# WX0_011_323DL.net
KiCad netlist of a schematic drawn in Altium Designer
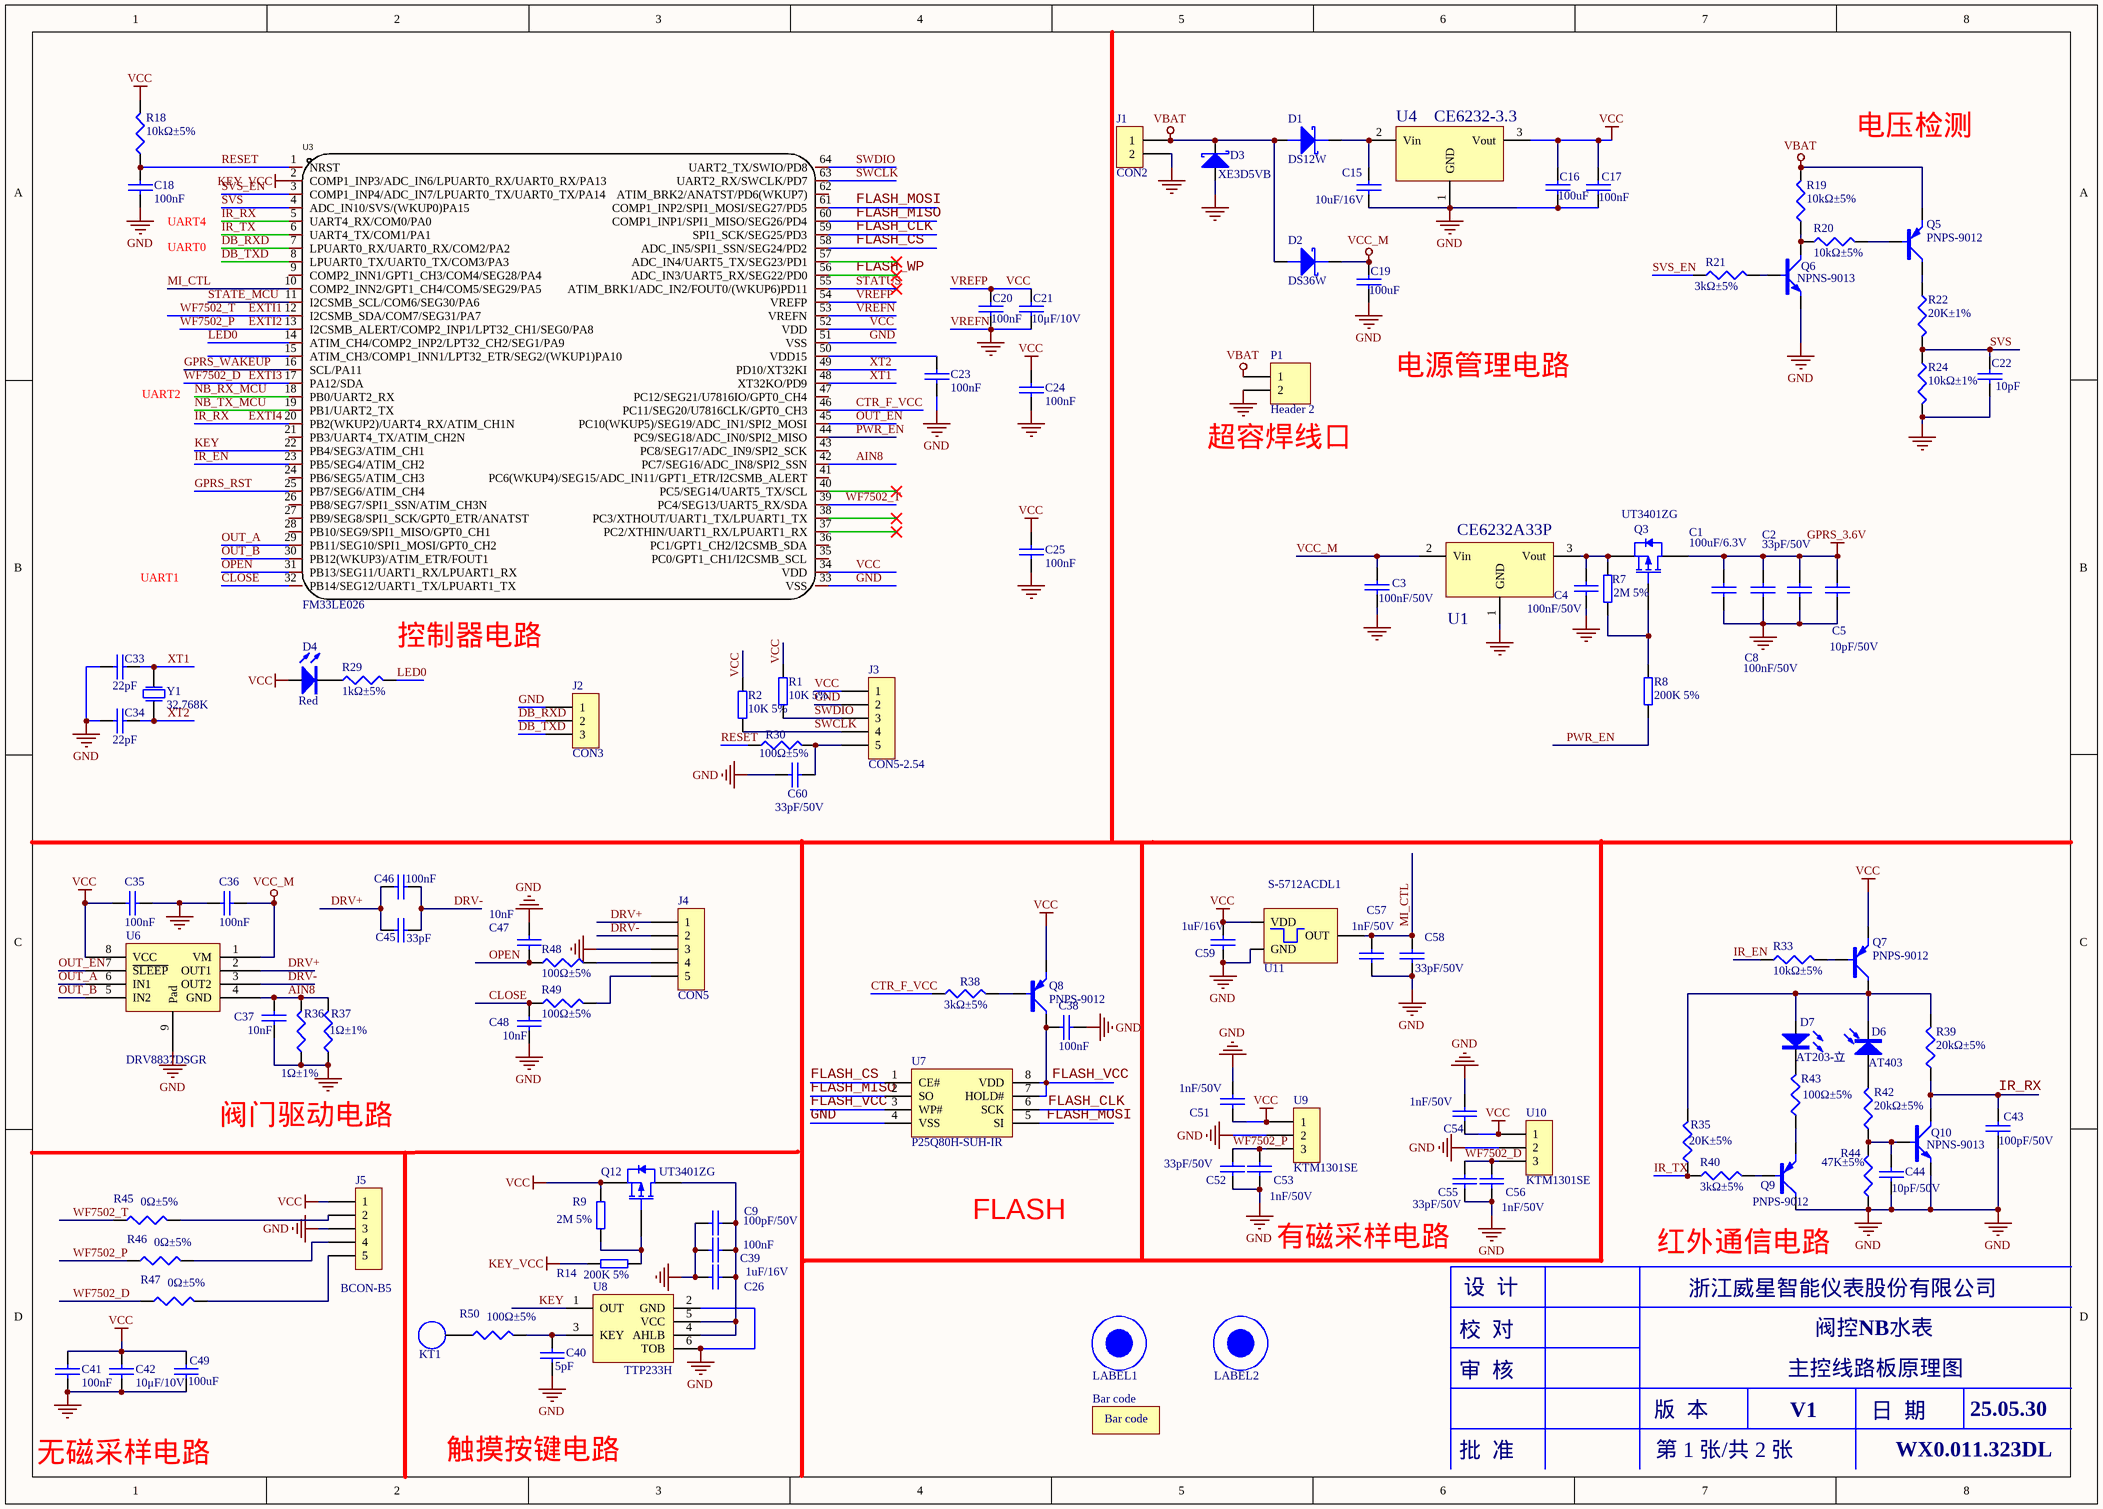
[diagram p0: WX0.011.323DL.SchDoc]

(export (version "E")
  (design (tool "Eeschema 10.0.6"))
  (components
    (comp (ref "Bar code")
      (value "Bar code")
      (footprint "Bar Code1")
      (libsource (lib "Connect_WX") (part "txm"))
    )
    (comp (ref "C1")
      (value "100uF/6.3V")
      (footprint "GRM1206")
      (description "100uF,6.3 V,±20%,1206,村田,GRM31CR60J107ME39L")
      (fields (field (name "PART NUMBER") "101020101-0020"))
      (libsource (lib "Database_Libs2") (part "CC06M5R5_107P"))
    )
    (comp (ref "C2")
      (value "33pF/50V")
      (footprint "CAP0603")
      (description "33pF,50 V,±10%,0603,国巨,CC0603KRNPO9BN33")
      (fields (field (name "PART NUMBER") "101020103-0027"))
      (libsource (lib "Database_Libs2") (part "CC03KPO9_33P"))
    )
    (comp (ref "C3")
      (value "100nF/50V")
      (footprint "CAP0603")
      (description "104pF,50 V,±10%,0603,国巨,CC0603KRX7R9BB104")
      (fields (field (name "PART NUMBER") "101020103-0021"))
      (libsource (lib "Database_Libs2") (part "CC03K7R9_100N"))
    )
    (comp (ref "C4")
      (value "100nF/50V")
      (footprint "CAP0603")
      (description "104pF,50 V,±10%,0603,国巨,CC0603KRX7R9BB104")
      (fields (field (name "PART NUMBER") "101020103-0021"))
      (libsource (lib "Database_Libs2") (part "CC03K7R9_100N"))
    )
    (comp (ref "C5")
      (value "10pF/50V")
      (footprint "CAP0603")
      (description "10pF,50 V,±5%,0603,X7R,国巨,CC0603JRNPO9BN100")
      (fields (field (name "PART NUMBER") "101020103-0014"))
      (libsource (lib "Database_Libs2") (part "CC03JPO9_10P"))
    )
    (comp (ref "C8")
      (value "100nF/50V")
      (footprint "CAP0603")
      (description "104pF,50 V,±10%,0603,国巨,CC0603KRX7R9BB104")
      (fields (field (name "PART NUMBER") "101020103-0021"))
      (libsource (lib "Database_Libs2") (part "CC03K7R9_100N"))
    )
    (comp (ref "C9")
      (value "100pF/50V")
      (footprint "CAP0603")
      (description "101pf,50 V,±5%,0603,国巨,CC0603JRNP09BN101")
      (fields (field (name "PART NUMBER") "101020103-0010"))
      (libsource (lib "Database_Libs2") (part "CC03JPO9_101P"))
    )
    (comp (ref "C15")
      (value "10uF/16V")
      (footprint "CAP0603")
      (description "105pF,16V,±10%,0603,国巨,CC0603KRX7R7BB105")
      (fields (field (name "PART NUMBER") "101020103-0003"))
      (libsource (lib "海外直通表U-GR3_GPRS") (part "CC03K7R7_1uF"))
    )
    (comp (ref "C16")
      (value "100uF")
      (footprint "GRM1206")
      (description "贴片电容,100uF±20%/6.3V,X5R,村田")
      (fields (field (name "PART NUMBER") "101020101-0020") (field (name "MANUFACTURER") "村田"))
      (libsource (lib "Devices") (part "CAP"))
    )
    (comp (ref "C17")
      (value "100nF")
      (footprint "CAP0603")
      (description "贴片电容,100nF±10%/50V,X7R,国巨")
      (fields (field (name "PART NUMBER") "101020103-0021") (field (name "MANUFACTURER") "国巨"))
      (libsource (lib "Devices") (part "CAP"))
    )
    (comp (ref "C18")
      (value "100nF")
      (footprint "CAP0603")
      (description "贴片电容,100nF±10%/50V,X7R,国巨")
      (fields (field (name "PART NUMBER") "101020103-0021") (field (name "MANUFACTURER") "国巨"))
      (libsource (lib "Devices") (part "CAP"))
    )
    (comp (ref "C19")
      (value "100uF")
      (footprint "GRM1206")
      (description "贴片电容,100uF±20%/6.3V,X5R,村田")
      (fields (field (name "PART NUMBER") "101020101-0020") (field (name "MANUFACTURER") "村田"))
      (libsource (lib "Devices") (part "CAP"))
    )
    (comp (ref "C20")
      (value "100nF")
      (footprint "CAP0603")
      (description "贴片电容,100nF±10%/50V,X7R,国巨")
      (fields (field (name "PART NUMBER") "101020103-0021") (field (name "MANUFACTURER") "国巨"))
      (libsource (lib "Devices") (part "CAP"))
    )
    (comp (ref "C21")
      (value "10μF/10V")
      (footprint "CAP0603")
      (description "贴片电容,10μF±10%/10V,X7R,村田")
      (fields (field (name "PART NUMBER") "101020103-0026") (field (name "MANUFACTURER") "村田"))
      (libsource (lib "Devices") (part "CAP"))
    )
    (comp (ref "C22")
      (value "10pF")
      (footprint "CAP0603")
      (description "贴片电容,12pF±5%/50V,NPO,国巨")
      (fields (field (name "PART NUMBER") "101020103-0005") (field (name "MANUFACTURER") "国巨"))
      (libsource (lib "Devices") (part "CAP"))
    )
    (comp (ref "C23")
      (value "100nF")
      (footprint "CAP0603")
      (description "贴片电容,100nF±10%/50V,X7R,国巨")
      (fields (field (name "PART NUMBER") "101020103-0021") (field (name "MANUFACTURER") "国巨"))
      (libsource (lib "Devices") (part "CAP"))
    )
    (comp (ref "C24")
      (value "100nF")
      (footprint "CAP0603")
      (description "贴片电容,100nF±10%/50V,X7R,国巨")
      (fields (field (name "PART NUMBER") "101020103-0021") (field (name "MANUFACTURER") "国巨"))
      (libsource (lib "Devices") (part "CAP"))
    )
    (comp (ref "C25")
      (value "100nF")
      (footprint "CAP0603")
      (description "贴片电容,100nF±10%/50V,X7R,国巨")
      (fields (field (name "PART NUMBER") "101020103-0021") (field (name "MANUFACTURER") "国巨"))
      (libsource (lib "Devices") (part "CAP"))
    )
    (comp (ref "C26")
      (value "1uF/16V")
      (footprint "CAP0603")
      (description "105pF,16 V,±10%,0603,国巨,CC0603KRX7R7BB105")
      (fields (field (name "PART NUMBER") "101020103-0003"))
      (libsource (lib "Database_Libs2") (part "CC03K7R7_1U"))
    )
    (comp (ref "C33")
      (value "22pF")
      (footprint "CAP0603")
      (description "贴片电容,22pF±5%/50V,NP0,国巨")
      (fields (field (name "PART NUMBER") "101020103-0009") (field (name "MANUFACTURER") "国巨"))
      (libsource (lib "Devices") (part "CAP"))
    )
    (comp (ref "C34")
      (value "22pF")
      (footprint "CAP0603")
      (description "贴片电容,22pF±5%/50V,NP0,国巨")
      (fields (field (name "PART NUMBER") "101020103-0009") (field (name "MANUFACTURER") "国巨"))
      (libsource (lib "Devices") (part "CAP"))
    )
    (comp (ref "C35")
      (value "100nF")
      (footprint "CAP0603")
      (description "贴片电容,100nF±10%/50V,X7R,国巨")
      (fields (field (name "PART NUMBER") "101020103-0021") (field (name "MANUFACTURER") "国巨"))
      (libsource (lib "Devices") (part "CAP"))
    )
    (comp (ref "C36")
      (value "100nF")
      (footprint "CAP0603")
      (description "贴片电容,100nF±10%/50V,X7R,国巨")
      (fields (field (name "PART NUMBER") "101020103-0021") (field (name "MANUFACTURER") "国巨"))
      (libsource (lib "Devices") (part "CAP"))
    )
    (comp (ref "C37")
      (value "10nF")
      (footprint "CAP0603")
      (description "贴片电容,10nF±10%/50V,X7R,国巨")
      (fields (field (name "PART NUMBER") "101020103-0007") (field (name "MANUFACTURER") "国巨"))
      (libsource (lib "Devices") (part "CAP"))
    )
    (comp (ref "C38")
      (value "100nF")
      (footprint "CAP0603")
      (description "贴片电容,100nF±10%/50V,X7R,国巨")
      (fields (field (name "PART NUMBER") "101020103-0021") (field (name "MANUFACTURER") "国巨"))
      (libsource (lib "Devices") (part "CAP"))
    )
    (comp (ref "C39")
      (value "100nF")
      (footprint "CAP0603")
      (description "贴片电容,100nF±10%/50V,X7R,国巨")
      (fields (field (name "PART NUMBER") "101020103-0021") (field (name "MANUFACTURER") "国巨"))
      (libsource (lib "Devices") (part "CAP"))
    )
    (comp (ref "C40")
      (value "5pF")
      (footprint "CAP0603")
      (description "贴片电容,4.7pF±0.25pF/50V,NPO,国巨")
      (fields (field (name "PART NUMBER") "101020103-0040") (field (name "MANUFACTURER") "国巨"))
      (libsource (lib "Devices") (part "CAP"))
    )
    (comp (ref "C41")
      (value "100nF")
      (footprint "CAP0603")
      (description "贴片电容,100nF±10%/50V,X7R,国巨")
      (fields (field (name "PART NUMBER") "101020103-0021") (field (name "MANUFACTURER") "国巨"))
      (libsource (lib "Devices") (part "CAP"))
    )
    (comp (ref "C42")
      (value "10μF/10V")
      (footprint "CAP0603")
      (description "贴片电容,1μF±10%/16V,X7R,国巨")
      (fields (field (name "PART NUMBER") "101020103-0003") (field (name "MANUFACTURER") "国巨"))
      (libsource (lib "Devices") (part "CAP"))
    )
    (comp (ref "C43")
      (value "100pF/50V")
      (footprint "CAP0603")
      (description "101pf,50 V,±5%,0603,国巨,CC0603JRNP09BN101")
      (fields (field (name "PART NUMBER") "101020103-0010"))
      (libsource (lib "Database_Libs2") (part "CC03JPO9_101P"))
    )
    (comp (ref "C44")
      (value "10pF/50V")
      (footprint "CAP0603")
      (description "10pF,50 V,±5%,0603,X7R,国巨,CC0603JRNPO9BN100")
      (fields (field (name "PART NUMBER") "101020103-0014"))
      (libsource (lib "Database_Libs2") (part "CC03JPO9_10P"))
    )
    (comp (ref "C45")
      (value "33pF")
      (footprint "CAP0603")
      (description "贴片电容,100nF±10%/50V,X7R,国巨")
      (fields (field (name "PART NUMBER") "101020103-0021") (field (name "MANUFACTURER") "国巨"))
      (libsource (lib "Devices") (part "CAP"))
    )
    (comp (ref "C46")
      (value "100nF")
      (footprint "CAP0603")
      (description "贴片电容,100nF±10%/50V,X7R,国巨")
      (fields (field (name "PART NUMBER") "101020103-0021") (field (name "MANUFACTURER") "国巨"))
      (libsource (lib "Devices") (part "CAP"))
    )
    (comp (ref "C47")
      (value "10nF")
      (footprint "CAP0603")
      (description "贴片电容,10nF±10%/50V,X7R,国巨")
      (fields (field (name "PART NUMBER") "101020103-0007") (field (name "MANUFACTURER") "国巨"))
      (libsource (lib "Devices") (part "CAP"))
    )
    (comp (ref "C48")
      (value "10nF")
      (footprint "CAP0603")
      (description "贴片电容,10nF±10%/50V,X7R,国巨")
      (fields (field (name "PART NUMBER") "101020103-0007") (field (name "MANUFACTURER") "国巨"))
      (libsource (lib "Devices") (part "CAP"))
    )
    (comp (ref "C49")
      (value "100uF")
      (footprint "GRM1206")
      (description "贴片电容,100uF±20%/6.3V,X5R,村田")
      (fields (field (name "PART NUMBER") "101020101-0020") (field (name "MANUFACTURER") "村田"))
      (libsource (lib "Devices") (part "CAP"))
    )
    (comp (ref "C51")
      (value "1nF/50V")
      (footprint "CAP0603")
      (description "102pF,50 V,±10%,0603,国巨,CC0603KRX7R9BB102")
      (fields (field (name "PART NUMBER") "101020103-0022"))
      (libsource (lib "Database_Libs2") (part "CC03K7R9_1N"))
    )
    (comp (ref "C52")
      (value "33pF/50V")
      (footprint "CAP0603")
      (description "33pF,50 V,±10%,0603,国巨,CC0603KRNPO9BN33")
      (fields (field (name "PART NUMBER") "101020103-0027"))
      (libsource (lib "Database_Libs2") (part "CC03KPO9_33P"))
    )
    (comp (ref "C53")
      (value "1nF/50V")
      (footprint "CAP0603")
      (description "102pF,50 V,±10%,0603,国巨,CC0603KRX7R9BB102")
      (fields (field (name "PART NUMBER") "101020103-0022"))
      (libsource (lib "Database_Libs2") (part "CC03K7R9_1N"))
    )
    (comp (ref "C54")
      (value "1nF/50V")
      (footprint "CAP0603")
      (description "102pF,50 V,±10%,0603,国巨,CC0603KRX7R9BB102")
      (fields (field (name "PART NUMBER") "101020103-0022"))
      (libsource (lib "Database_Libs2") (part "CC03K7R9_1N"))
    )
    (comp (ref "C55")
      (value "33pF/50V")
      (footprint "CAP0603")
      (description "33pF,50 V,±10%,0603,国巨,CC0603KRNPO9BN33")
      (fields (field (name "PART NUMBER") "101020103-0027"))
      (libsource (lib "Database_Libs2") (part "CC03KPO9_33P"))
    )
    (comp (ref "C56")
      (value "1nF/50V")
      (footprint "CAP0603")
      (description "102pF,50 V,±10%,0603,国巨,CC0603KRX7R9BB102")
      (fields (field (name "PART NUMBER") "101020103-0022"))
      (libsource (lib "Database_Libs2") (part "CC03K7R9_1N"))
    )
    (comp (ref "C57")
      (value "1nF/50V")
      (footprint "CAP0603")
      (description "102pF,50 V,±10%,0603,国巨,CC0603KRX7R9BB102")
      (fields (field (name "PART NUMBER") "101020103-0022"))
      (libsource (lib "Database_Libs2") (part "CC03K7R9_1N"))
    )
    (comp (ref "C58")
      (value "33pF/50V")
      (footprint "CAP0603")
      (description "33pF,50 V,±10%,0603,国巨,CC0603KRNPO9BN33")
      (fields (field (name "PART NUMBER") "101020103-0027"))
      (libsource (lib "Database_Libs2") (part "CC03KPO9_33P"))
    )
    (comp (ref "C59")
      (value "1uF/16V")
      (footprint "CAP0603")
      (description "105pF,16 V,±10%,0603,国巨,CC0603KRX7R7BB105")
      (fields (field (name "PART NUMBER") "101020103-0003"))
      (libsource (lib "Database_Libs2") (part "CC03K7R7_1U"))
    )
    (comp (ref "C60")
      (value "33pF/50V")
      (footprint "CAP0603")
      (description "33pF,50 V,±10%,0603,国巨,CC0603KRNPO9BN33")
      (fields (field (name "PART NUMBER") "101020103-0027"))
      (libsource (lib "Database_Libs2") (part "CC03KPO9_33P"))
    )
    (comp (ref "D1")
      (value "DS12W")
      (footprint "SOD-123FL")
      (description "DS36W,SOD123-FL,3 A,42 V,60 V,浙江领晨科技有限公司,DS36W")
      (fields (field (name "PART NUMBER") "101040101-0055"))
      (libsource (lib "Database_Libs2") (part "02_DS36W"))
    )
    (comp (ref "D2")
      (value "DS36W")
      (footprint "SOD-123FL")
      (description "DS36W,SOD123-FL,3 A,42 V,60 V,浙江领晨科技有限公司,DS36W")
      (fields (field (name "PART NUMBER") "101040101-0055"))
      (libsource (lib "Database_Libs2") (part "02_DS36W"))
    )
    (comp (ref "D3")
      (value "XE3D5VB")
      (footprint "SOD-323_L1.8-W1.3-LS2.5-RD")
      (description "具有3.5pF低结电容，适用于IO线、电源线、高速信号的ESD二极管阵列,SOD-323,5 V,5 V,350 W,5 A,1 uA,矽航,XE3D5VB")
      (fields (field (name "PART NUMBER") "101040104-0010") (field (name "MANUFACTURER") "矽航"))
      (libsource (lib "Devices") (part "DIODE1"))
    )
    (comp (ref "D4")
      (value "Red")
      (footprint "LED-0603")
      (description "发光二极管,红色,0603,光宝")
      (fields (field (name "PART NUMBER") "101040102-0006") (field (name "MANUFACTURER") "光宝"))
      (libsource (lib "Devices") (part "LED"))
    )
    (comp (ref "D6")
      (value "AT403")
      (footprint "LED2_300")
      (description "红外接收头，插件，红光，AT403_PD_01")
      (fields (field (name "PART NUMBER") "101040102-0011") (field (name "MANUFACTURER") "品观"))
      (libsource (lib "Devices") (part "LED_IN"))
    )
    (comp (ref "D7")
      (value "AT203-立")
      (footprint "LED2_300")
      (description "红外发射头，插件，红光，AT203")
      (fields (field (name "PART NUMBER") "101040102-0010") (field (name "MANUFACTURER") "品观"))
      (libsource (lib "") (part "LED_1"))
    )
    (comp (ref "J1")
      (value "CON2")
      (footprint "SIP-2")
      (description "焊接插座,间距2.54mm")
      (libsource (lib "Devices") (part "CON2"))
    )
    (comp (ref "J2")
      (value "CON3")
      (footprint "SIP-3")
      (description "焊接插座,间距2.54mm")
      (libsource (lib "Devices") (part "CON3"))
    )
    (comp (ref "J3")
      (value "CON5-2.54")
      (footprint "PIN254_1*5*1100S")
      (description "焊接插座,间距2.0mm")
      (libsource (lib "Devices") (part "CON5"))
    )
    (comp (ref "J4")
      (value "CON5")
      (footprint "PIN254_1*5*1100S")
      (description "焊接插座,间距2.54mm")
      (libsource (lib "Devices") (part "CON5"))
    )
    (comp (ref "J5")
      (value "BCON-B5")
      (footprint "J_DIP_2.0_1*05_H")
      (description "焊接插座,90度插板双面焊盘,公头,间距1.5mm")
      (libsource (lib "Devices") (part "CON5"))
    )
    (comp (ref "KT1")
      (value "Touch")
      (footprint "TOUCH-1")
      (description "按键,6mm弹簧按键,按键直径10mm")
      (fields (field (name "PART NUMBER") "1011001-0060"))
      (libsource (lib "Devices") (part "TOUCHKEY"))
    )
    (comp (ref "LABEL1")
      (value "~")
      (footprint "MARK")
      (description "标准Mark点,直径1mm,阻焊开窗3mm")
      (libsource (lib "Devices") (part "MARK"))
    )
    (comp (ref "LABEL2")
      (value "~")
      (footprint "MARK")
      (description "标准Mark点,直径1mm,阻焊开窗3mm")
      (libsource (lib "Devices") (part "MARK"))
    )
    (comp (ref "P1") (value "Header 2") (footprint "SIP-2") (libsource (lib "Connect_WX") (part "Header 2")))
    (comp (ref "Q3")
      (value "UT3401ZG")
      (footprint "SOT-23")
      (description "UT3401ZG,P-MOS,SOT-23,UTC,UT3401ZG")
      (fields (field (name "PART NUMBER") "101040201-0013"))
      (libsource (lib "Database_Libs2") (part "03_P-UT3401ZG"))
    )
    (comp (ref "Q5")
      (value "PNPS-9012")
      (footprint "SOT-23")
      (description "9012,PNP,SOT-23,JCET;长电,S9012")
      (fields (field (name "PART NUMBER") "101040201-0001"))
      (libsource (lib "Database_Libs2") (part "03_PNPS-9012"))
    )
    (comp (ref "Q6")
      (value "NPNS-9013")
      (footprint "SOT-23")
      (description "9013,NPN,SOT-23,长电,S9013")
      (fields (field (name "PART NUMBER") "101040201-0002"))
      (libsource (lib "Database_Libs2") (part "03_NPNS-9013"))
    )
    (comp (ref "Q7")
      (value "PNPS-9012")
      (footprint "SOT-23")
      (description "9012,PNP,SOT-23,JCET;长电,S9012")
      (fields (field (name "PART NUMBER") "101040201-0001"))
      (libsource (lib "Database_Libs2") (part "03_PNPS-9012"))
    )
    (comp (ref "Q8")
      (value "PNPS-9012")
      (footprint "SOT-23")
      (description "9012,PNP,SOT-23,JCET;长电,S9012")
      (fields (field (name "PART NUMBER") "101040201-0001"))
      (libsource (lib "Database_Libs2") (part "03_PNPS-9012"))
    )
    (comp (ref "Q9")
      (value "PNPS-9012")
      (footprint "SOT-23")
      (description "9012,PNP,SOT-23,JCET;长电,S9012")
      (fields (field (name "PART NUMBER") "101040201-0001"))
      (libsource (lib "Database_Libs2") (part "03_PNPS-9012"))
    )
    (comp (ref "Q10")
      (value "NPNS-9013")
      (footprint "SOT-23")
      (description "9013,NPN,SOT-23,长电,S9013")
      (fields (field (name "PART NUMBER") "101040201-0002"))
      (libsource (lib "Database_Libs2") (part "03_NPNS-9013"))
    )
    (comp (ref "Q12")
      (value "UT3401ZG")
      (footprint "SOT-23")
      (description "UT3401ZG,P-MOS,SOT-23,UTC,UT3401ZG")
      (fields (field (name "PART NUMBER") "101040201-0013"))
      (libsource (lib "Database_Libs2") (part "03_P-UT3401ZG"))
    )
    (comp (ref "R1")
      (value "10K 5%")
      (footprint "RES0603")
      (description "国巨,±5%,0603,,155 ℃,-55 ℃,RC0603JR-0710KL,无铅,200 ppm/℃,1/10W,,10K")
      (fields (field (name "PART NUMBER") "101010103-0003"))
      (libsource (lib "Database_Libs2") (part "RC03J_10K"))
    )
    (comp (ref "R2")
      (value "10K 5%")
      (footprint "RES0603")
      (description "国巨,±5%,0603,,155 ℃,-55 ℃,RC0603JR-0710KL,无铅,200 ppm/℃,1/10W,,10K")
      (fields (field (name "PART NUMBER") "101010103-0003"))
      (libsource (lib "Database_Libs2") (part "RC03J_10K"))
    )
    (comp (ref "R7")
      (value "2M 5%")
      (footprint "RES0603")
      (description "国巨,±5%,0603,,155 ℃,-55 ℃,RC0603JR-072ML,含铅,100 ppm/℃,1/10W,,2M")
      (fields (field (name "PART NUMBER") "101010103-0025"))
      (libsource (lib "Database_Libs2") (part "RC03J_2M"))
    )
    (comp (ref "R8")
      (value "200K 5%")
      (footprint "RES0603")
      (description "200K,±5%,1/10W,0603,国巨,RC0603JR-07200KL")
      (fields (field (name "PART NUMBER") "101010103-0034"))
      (libsource (lib "Database_Libs2") (part "RC03J_200K"))
    )
    (comp (ref "R9")
      (value "2M 5%")
      (footprint "RES0603")
      (description "国巨,±5%,0603,,155 ℃,-55 ℃,RC0603JR-072ML,含铅,100 ppm/℃,1/10W,,2M")
      (fields (field (name "PART NUMBER") "101010103-0025"))
      (libsource (lib "Database_Libs2") (part "RC03J_2M"))
    )
    (comp (ref "R14")
      (value "200K 5%")
      (footprint "RES0603")
      (description "200K,±5%,1/10W,0603,国巨,RC0603JR-07200KL")
      (fields (field (name "PART NUMBER") "101010103-0034"))
      (libsource (lib "Database_Libs2") (part "RC03J_200K"))
    )
    (comp (ref "R18")
      (value "10kΩ±5%")
      (footprint "RES0603")
      (description "贴片电阻,10kΩ±5%,1/10W,100ppm/℃,国巨")
      (fields (field (name "PART NUMBER") "101010103-0003") (field (name "MANUFACTURER") "国巨"))
      (libsource (lib "Devices") (part "RES1"))
    )
    (comp (ref "R19")
      (value "10kΩ±5%")
      (footprint "RES0603")
      (description "贴片电阻,10kΩ±5%,1/10W,100ppm/℃,国巨")
      (fields (field (name "PART NUMBER") "101010103-0003") (field (name "MANUFACTURER") "国巨"))
      (libsource (lib "Devices") (part "RES1"))
    )
    (comp (ref "R20")
      (value "10kΩ±5%")
      (footprint "RES0603")
      (description "贴片电阻,10kΩ±5%,1/10W,100ppm/℃,国巨")
      (fields (field (name "PART NUMBER") "101010103-0003") (field (name "MANUFACTURER") "国巨"))
      (libsource (lib "Devices") (part "RES1"))
    )
    (comp (ref "R21")
      (value "3kΩ±5%")
      (footprint "RES0603")
      (description "贴片电阻,4.7kΩ±5%,1/10W,100ppm/℃,国巨")
      (fields (field (name "PART NUMBER") "101010103-0042") (field (name "MANUFACTURER") "国巨"))
      (libsource (lib "Devices") (part "RES1"))
    )
    (comp (ref "R22")
      (value "20K±1%")
      (footprint "RES0603")
      (description "贴片电阻，20K,±1%,1/10W,0603,国巨,RC0603FR-0720KL")
      (fields (field (name "PART NUMBER") "101010103-0048") (field (name "MANUFACTURER") "国巨"))
      (libsource (lib "Devices") (part "RES1"))
    )
    (comp (ref "R24")
      (value "10kΩ±1%")
      (footprint "RES0603")
      (description "贴片电阻,10kΩ±1%,1/10W,100ppm/℃,国巨")
      (fields (field (name "PART NUMBER") "101010103-0052") (field (name "MANUFACTURER") "国巨"))
      (libsource (lib "Devices") (part "RES1"))
    )
    (comp (ref "R29")
      (value "1kΩ±5%")
      (footprint "RES0603")
      (description "贴片电阻,1kΩ±5%,1/10W,100ppm/℃,国巨")
      (fields (field (name "PART NUMBER") "101010103-0008") (field (name "MANUFACTURER") "国巨"))
      (libsource (lib "Devices") (part "RES1"))
    )
    (comp (ref "R30")
      (value "100Ω±5%")
      (footprint "RES0603")
      (description "贴片电阻,0Ω±5%,1/10W,100ppm/℃,国巨")
      (fields (field (name "PART NUMBER") "101010103-0001") (field (name "MANUFACTURER") "国巨"))
      (libsource (lib "Devices") (part "RES1"))
    )
    (comp (ref "R33")
      (value "10kΩ±5%")
      (footprint "RES0603")
      (description "贴片电阻,1kΩ±5%,1/10W,100ppm/℃,国巨")
      (fields (field (name "PART NUMBER") "101010103-0008") (field (name "MANUFACTURER") "国巨"))
      (libsource (lib "Devices") (part "RES1"))
    )
    (comp (ref "R35")
      (value "20K±5%")
      (footprint "RES0603")
      (description "贴片电阻,1MΩ±5%,1/10W,100ppm/℃,国巨")
      (fields (field (name "PART NUMBER") "101010103-0002") (field (name "MANUFACTURER") "国巨"))
      (libsource (lib "Devices") (part "RES1"))
    )
    (comp (ref "R36")
      (value "1Ω±1%")
      (footprint "R1206")
      (description "贴片电阻，1Ω±1%,1/4W,1206,国巨,RC1206FR-071RL")
      (fields (field (name "PART NUMBER") "101010101-0034") (field (name "MANUFACTURER") "国巨"))
      (libsource (lib "Devices") (part "RES1"))
    )
    (comp (ref "R37")
      (value "1Ω±1%")
      (footprint "R1206")
      (description "贴片电阻，1Ω±1%,1/4W,1206,国巨,RC1206FR-071RL")
      (fields (field (name "PART NUMBER") "101010101-0034") (field (name "MANUFACTURER") "国巨"))
      (libsource (lib "Devices") (part "RES1"))
    )
    (comp (ref "R38")
      (value "3kΩ±5%")
      (footprint "RES0603")
      (description "贴片电阻,10kΩ±5%,1/10W,100ppm/℃,国巨")
      (fields (field (name "PART NUMBER") "101010103-0003") (field (name "MANUFACTURER") "国巨"))
      (libsource (lib "Devices") (part "RES1"))
    )
    (comp (ref "R39")
      (value "20kΩ±5%")
      (footprint "RES0603")
      (description "贴片电阻,100kΩ±5%,1/10W,100ppm/℃,国巨")
      (fields (field (name "PART NUMBER") "101010103-0005") (field (name "MANUFACTURER") "国巨"))
      (libsource (lib "Devices") (part "RES1"))
    )
    (comp (ref "R40")
      (value "3kΩ±5%")
      (footprint "RES0603")
      (description "贴片电阻,1kΩ±5%,1/10W,100ppm/℃,国巨")
      (fields (field (name "PART NUMBER") "101010103-0008") (field (name "MANUFACTURER") "国巨"))
      (libsource (lib "Devices") (part "RES1"))
    )
    (comp (ref "R42")
      (value "20kΩ±5%")
      (footprint "RES0603")
      (description "贴片电阻,20kΩ±5%,1/10W,100ppm/℃,国巨")
      (fields (field (name "PART NUMBER") "101010103-0004") (field (name "MANUFACTURER") "国巨"))
      (libsource (lib "Devices") (part "RES1"))
    )
    (comp (ref "R43")
      (value "100Ω±5%")
      (footprint "RES0603")
      (description "贴片电阻,100Ω±5%,1/10W,100ppm/℃,国巨")
      (fields (field (name "PART NUMBER") "101010103-0022") (field (name "MANUFACTURER") "国巨"))
      (libsource (lib "Devices") (part "RES1"))
    )
    (comp (ref "R44")
      (value "47K±5%")
      (footprint "RES0603")
      (description "贴片电阻，47K,±5%,1/10W,0603,国巨,RC0603JR-0747KL")
      (fields (field (name "PART NUMBER") "101010103-0012") (field (name "MANUFACTURER") "国巨"))
      (libsource (lib "Devices") (part "RES1"))
    )
    (comp (ref "R45")
      (value "0Ω±5%")
      (footprint "RES0603")
      (description "贴片电阻,100Ω±5%,1/10W,100ppm/℃,国巨")
      (fields (field (name "PART NUMBER") "101010103-0022") (field (name "MANUFACTURER") "国巨"))
      (libsource (lib "Devices") (part "RES1"))
    )
    (comp (ref "R46")
      (value "0Ω±5%")
      (footprint "RES0603")
      (description "贴片电阻,100Ω±5%,1/10W,100ppm/℃,国巨")
      (fields (field (name "PART NUMBER") "101010103-0022") (field (name "MANUFACTURER") "国巨"))
      (libsource (lib "Devices") (part "RES1"))
    )
    (comp (ref "R47")
      (value "0Ω±5%")
      (footprint "RES0603")
      (description "贴片电阻,100Ω±5%,1/10W,100ppm/℃,国巨")
      (fields (field (name "PART NUMBER") "101010103-0022") (field (name "MANUFACTURER") "国巨"))
      (libsource (lib "Devices") (part "RES1"))
    )
    (comp (ref "R48")
      (value "100Ω±5%")
      (footprint "RES0603")
      (description "贴片电阻,100Ω±5%,1/10W,100ppm/℃,国巨")
      (fields (field (name "PART NUMBER") "101010103-0022") (field (name "MANUFACTURER") "国巨"))
      (libsource (lib "Devices") (part "RES1"))
    )
    (comp (ref "R49")
      (value "100Ω±5%")
      (footprint "RES0603")
      (description "贴片电阻,100Ω±5%,1/10W,100ppm/℃,国巨")
      (fields (field (name "PART NUMBER") "101010103-0022") (field (name "MANUFACTURER") "国巨"))
      (libsource (lib "Devices") (part "RES1"))
    )
    (comp (ref "R50")
      (value "100Ω±5%")
      (footprint "RES0603")
      (description "贴片电阻,100Ω±5%,1/10W,100ppm/℃,国巨")
      (fields (field (name "PART NUMBER") "101010103-0022") (field (name "MANUFACTURER") "国巨"))
      (libsource (lib "Devices") (part "RES1"))
    )
    (comp (ref "U1")
      (value "CE6232A33P")
      (footprint "SOT-89")
      (description "CE6232-3.3,CE6232-3.3,SOT89-3,8V,1.8V,0.11V,3.3V,300mA,0.8uA,南京芯力微电子有限公司")
      (fields (field (name "PART NUMBER") "1010503-0029"))
      (libsource (lib "Database_Libs2") (part "02_CE6232A33P"))
    )
    (comp (ref "U3")
      (value "FM33LE026")
      (footprint "LQFP-64_L10.0-W10.0-P0.50-LS12.0-BL")
      (description "单片机,FM33LE026,复旦微")
      (fields (field (name "MANUFACTURER") "复旦微") (field (name "MANUFACTURER PART") "FM33LC026N"))
      (libsource (lib "Devices") (part "FM33LE026"))
    )
    (comp (ref "U4")
      (value "CE6232-3.3")
      (footprint "SOT-89")
      (description "CE6232-3.3,CE6232-3.3,SOT89-3,8V,1.8V,0.11V,3.3V,300mA,0.8uA,南京芯力微电子有限公司")
      (fields (field (name "PART NUMBER") "1010503-0029"))
      (libsource (lib "海外直通表U-GR3_GPRS") (part "02_CE6232-3.3"))
    )
    (comp (ref "U6")
      (value "DRV8837DSGR")
      (footprint "S-PWSON-N8")
      (description "DRV8837DSGR,S-PWSON-N8,TI,DRV8837DSGR")
      (fields (field (name "PART NUMBER") "101050101-0060"))
      (libsource (lib "海外直通表U-GR3_GPRS") (part "07_DRV8837DSGR"))
    )
    (comp (ref "U7")
      (value "P25Q80H-SUH-IR")
      (footprint "SOP-8L-200MIL")
      (description "P25Q80H-SUH-IR,SOP8 208mil,普冉半导体（上海）股份有限公司,P25Q80H-SUH-IR")
      (fields (field (name "PART NUMBER") "101050101-0218"))
      (libsource (lib "海外直通表U-GR3_GPRS") (part "04_P25Q80H-SUH-IR"))
    )
    (comp (ref "U8")
      (value "TTP233H")
      (footprint "SOT-23-6")
      (description "集成电路，TTP233H,TONTEK")
      (fields (field (name "PART NUMBER") "101050101-0262") (field (name "MANUFACTURER") "TONTEK"))
      (libsource (lib "Devices") (part "TTP233H"))
    )
    (comp (ref "U9")
      (value "KTM1301SE")
      (footprint "ESP3_QYSW_JSZ")
      (description "昆泰KTM1301SE（插件）")
      (libsource (lib "Devices") (part "CON3"))
    )
    (comp (ref "U10")
      (value "KTM1301SE")
      (footprint "ESP3_QYSW_JSZ")
      (description "昆泰KTM1301SE（插件）")
      (libsource (lib "Devices") (part "CON3"))
    )
    (comp (ref "U11")
      (value "S-5712ACDL1")
      (footprint "SOT-23")
      (description "S-5712ACDL1,SOT23-3,3.5 V,1.6 V,2 uA,精工电子,S-5712ACDL1")
      (fields (field (name "PART NUMBER") "1010504-0002"))
      (libsource (lib "Database_Libs2") (part "01_S-5712ACDL1"))
    )
    (comp (ref "Y1")
      (value "32.768K")
      (footprint "SMD-3215_2P")
      (description "晶振,32.768KHz,±20ppm,12.5pF,3215,EPSON")
      (fields (field (name "PART NUMBER") "1010601-0009") (field (name "MANUFACTURER") "EPSON"))
      (libsource (lib "Devices") (part "XTAL"))
    )
  )
  (nets
    (net (code "1") (name "/AIN8") (class "Default")
      (node (ref "C37") (pin "2") (pinfunction "2_2") (pintype "passive"))
      (node (ref "R36") (pin "2") (pinfunction "2_2") (pintype "passive"))
      (node (ref "R37") (pin "2") (pinfunction "2_2") (pintype "passive"))
      (node (ref "U3") (pin "42") (pinfunction "PC7/SEG16/ADC_IN8/SPI2_SSN_42") (pintype "passive"))
      (node (ref "U6") (pin "4") (pinfunction "GND_4") (pintype "passive"))
    )
    (net (code "2") (name "/CLOSE") (class "Default")
      (node (ref "C48") (pin "2") (pinfunction "2_2") (pintype "passive"))
      (node (ref "R49") (pin "1") (pinfunction "1_1") (pintype "passive"))
      (node (ref "U3") (pin "32") (pinfunction "PB14/SEG12/UART1_TX/LPUART1_TX_32") (pintype "passive"))
    )
    (net (code "3") (name "/CTR_F_VCC") (class "Default")
      (node (ref "R38") (pin "1") (pinfunction "1_1") (pintype "passive"))
      (node (ref "U3") (pin "46") (pinfunction "PC11/SEG20/U7816CLK/GPT0_CH3_46") (pintype "passive"))
    )
    (net (code "4") (name "/DB_RXD") (class "Default")
      (node (ref "J2") (pin "2") (pinfunction "2_2") (pintype "passive"))
      (node (ref "U3") (pin "7") (pinfunction "LPUART0_RX/UART0_RX/COM2/PA2_7") (pintype "passive"))
    )
    (net (code "5") (name "/DB_TXD") (class "Default")
      (node (ref "J2") (pin "3") (pinfunction "3_3") (pintype "passive"))
      (node (ref "U3") (pin "8") (pinfunction "LPUART0_TX/UART0_TX/COM3/PA3_8") (pintype "passive"))
    )
    (net (code "6") (name "/DRV+") (class "Default")
      (node (ref "C45") (pin "2") (pinfunction "2_2") (pintype "passive"))
      (node (ref "C46") (pin "2") (pinfunction "2_2") (pintype "passive"))
      (node (ref "J4") (pin "1") (pinfunction "1_1") (pintype "passive"))
      (node (ref "U6") (pin "2") (pinfunction "OUT1_2") (pintype "passive"))
    )
    (net (code "7") (name "/DRV-") (class "Default")
      (node (ref "C45") (pin "1") (pinfunction "1_1") (pintype "passive"))
      (node (ref "C46") (pin "1") (pinfunction "1_1") (pintype "passive"))
      (node (ref "J4") (pin "2") (pinfunction "2_2") (pintype "passive"))
      (node (ref "U6") (pin "3") (pinfunction "OUT2_3") (pintype "passive"))
    )
    (net (code "8") (name "/EXTI1") (class "Default")
      (node (ref "R45") (pin "1") (pinfunction "1_1") (pintype "passive"))
      (node (ref "U3") (pin "12") (pinfunction "I2CSMB_SDA/COM7/SEG31/PA7_12") (pintype "passive"))
      (node (ref "U3") (pin "39") (pinfunction "PC4/SEG13/UART5_RX/SDA_39") (pintype "passive"))
    )
    (net (code "9") (name "/EXTI2") (class "Default")
      (node (ref "C52") (pin "1") (pinfunction "1_1") (pintype "passive"))
      (node (ref "C53") (pin "1") (pinfunction "1_1") (pintype "passive"))
      (node (ref "R46") (pin "1") (pinfunction "1_1") (pintype "passive"))
      (node (ref "U3") (pin "13") (pinfunction "I2CSMB_ALERT/COMP2_INP1/LPT32_CH1/SEG0/PA8_13") (pintype "passive"))
      (node (ref "U9") (pin "3") (pinfunction "3_3") (pintype "passive"))
    )
    (net (code "10") (name "/EXTI3") (class "Default")
      (node (ref "C55") (pin "1") (pinfunction "1_1") (pintype "passive"))
      (node (ref "C56") (pin "1") (pinfunction "1_1") (pintype "passive"))
      (node (ref "R47") (pin "1") (pinfunction "1_1") (pintype "passive"))
      (node (ref "U10") (pin "3") (pinfunction "3_3") (pintype "passive"))
      (node (ref "U3") (pin "17") (pinfunction "PA12/SDA_17") (pintype "passive"))
    )
    (net (code "11") (name "/EXTI4") (class "Default")
      (node (ref "C43") (pin "1") (pinfunction "1_1") (pintype "passive"))
      (node (ref "Q10") (pin "3") (pinfunction "C_3") (pintype "passive"))
      (node (ref "R39") (pin "1") (pinfunction "1_1") (pintype "passive"))
      (node (ref "U3") (pin "20") (pinfunction "PB2(WKUP2)/UART4_RX/ATIM_CH1N_20") (pintype "passive"))
      (node (ref "U3") (pin "5") (pinfunction "UART4_RX/COM0/PA0_5") (pintype "passive"))
    )
    (net (code "12") (name "/FLASH_CLK") (class "Default")
      (node (ref "U3") (pin "59") (pinfunction "SPI1_SCK/SEG25/PD3_59") (pintype "passive"))
      (node (ref "U7") (pin "6") (pinfunction "SCK_6") (pintype "passive"))
    )
    (net (code "13") (name "/FLASH_CS") (class "Default")
      (node (ref "U3") (pin "58") (pinfunction "ADC_IN5/SPI1_SSN/SEG24/PD2_58") (pintype "passive"))
      (node (ref "U7") (pin "1") (pinfunction "CE#_1") (pintype "passive"))
    )
    (net (code "14") (name "/FLASH_MISO") (class "Default")
      (node (ref "U3") (pin "60") (pinfunction "COMP1_INP1/SPI1_MISO/SEG26/PD4_60") (pintype "passive"))
      (node (ref "U7") (pin "2") (pinfunction "SO_2") (pintype "passive"))
    )
    (net (code "15") (name "/FLASH_MOSI") (class "Default")
      (node (ref "U3") (pin "61") (pinfunction "COMP1_INP2/SPI1_MOSI/SEG27/PD5_61") (pintype "passive"))
      (node (ref "U7") (pin "5") (pinfunction "SI_5") (pintype "passive"))
    )
    (net (code "16") (name "/FLASH_VCC") (class "Default")
      (node (ref "C38") (pin "2") (pinfunction "2_2") (pintype "passive"))
      (node (ref "Q8") (pin "3") (pinfunction "C_3") (pintype "passive"))
      (node (ref "U7") (pin "3") (pinfunction "WP#_3") (pintype "passive"))
      (node (ref "U7") (pin "7") (pinfunction "HOLD#_7") (pintype "passive"))
      (node (ref "U7") (pin "8") (pinfunction "VDD_8") (pintype "passive"))
    )
    (net (code "17") (name "/FLASH_WP") (class "Default")
      (node (ref "U3") (pin "56") (pinfunction "ADC_IN3/UART5_RX/SEG22/PD0_56") (pintype "passive+no_connect"))
    )
    (net (code "18") (name "/GPRS_RST") (class "Default")
      (node (ref "U3") (pin "25") (pinfunction "PB7/SEG6/ATIM_CH4_25") (pintype "passive"))
    )
    (net (code "19") (name "/GPRS_WAKEUP") (class "Default")
      (node (ref "U3") (pin "16") (pinfunction "SCL/PA11_16") (pintype "passive"))
    )
    (net (code "20") (name "/IR_EN") (class "Default")
      (node (ref "R33") (pin "1") (pinfunction "1_1") (pintype "passive"))
      (node (ref "U3") (pin "23") (pinfunction "PB5/SEG4/ATIM_CH2_23") (pintype "passive"))
    )
    (net (code "21") (name "/IR_TX") (class "Default")
      (node (ref "R35") (pin "1") (pinfunction "1_1") (pintype "passive"))
      (node (ref "R40") (pin "1") (pinfunction "1_1") (pintype "passive"))
      (node (ref "U3") (pin "6") (pinfunction "UART4_TX/COM1/PA1_6") (pintype "passive"))
    )
    (net (code "22") (name "/KEY") (class "Default")
      (node (ref "U3") (pin "22") (pinfunction "PB4/SEG3/ATIM_CH1_22") (pintype "passive"))
      (node (ref "U8") (pin "1") (pinfunction "OUT_1") (pintype "passive"))
    )
    (net (code "23") (name "/LED0") (class "Default")
      (node (ref "R29") (pin "2") (pinfunction "2_2") (pintype "passive"))
      (node (ref "U3") (pin "14") (pinfunction "ATIM_CH4/COMP2_INP2/LPT32_CH2/SEG1/PA9_14") (pintype "passive"))
    )
    (net (code "24") (name "/MI_CTL") (class "Default")
      (node (ref "C57") (pin "1") (pinfunction "1_1") (pintype "passive"))
      (node (ref "C58") (pin "1") (pinfunction "1_1") (pintype "passive"))
      (node (ref "U11") (pin "2") (pinfunction "OUT_2") (pintype "passive"))
      (node (ref "U3") (pin "10") (pinfunction "COMP2_INN2/GPT1_CH4/COM5/SEG29/PA5_10") (pintype "passive"))
    )
    (net (code "25") (name "/NB_RX_MCU") (class "Default")
      (node (ref "U3") (pin "18") (pinfunction "PB0/UART2_RX_18") (pintype "passive"))
    )
    (net (code "26") (name "/NB_TX_MCU") (class "Default")
      (node (ref "U3") (pin "19") (pinfunction "PB1/UART2_TX_19") (pintype "passive"))
    )
    (net (code "27") (name "/OPEN") (class "Default")
      (node (ref "C47") (pin "1") (pinfunction "1_1") (pintype "passive"))
      (node (ref "R48") (pin "1") (pinfunction "1_1") (pintype "passive"))
      (node (ref "U3") (pin "31") (pinfunction "PB13/SEG11/UART1_RX/LPUART1_RX_31") (pintype "passive"))
    )
    (net (code "28") (name "/OUT_A") (class "Default")
      (node (ref "U3") (pin "29") (pinfunction "PB11/SEG10/SPI1_MOSI/GPT0_CH2_29") (pintype "passive"))
      (node (ref "U6") (pin "6") (pinfunction "IN1_6") (pintype "passive"))
    )
    (net (code "29") (name "/OUT_B") (class "Default")
      (node (ref "U3") (pin "30") (pinfunction "PB12(WKUP3)/ATIM_ETR/FOUT1_30") (pintype "passive"))
      (node (ref "U6") (pin "5") (pinfunction "IN2_5") (pintype "passive"))
    )
    (net (code "30") (name "/OUT_EN") (class "Default")
      (node (ref "U3") (pin "45") (pinfunction "PC10(WKUP5)/SEG19/ADC_IN1/SPI2_MOSI_45") (pintype "passive"))
      (node (ref "U6") (pin "7") (pinfunction "~{SLEEP}_7") (pintype "passive"))
    )
    (net (code "31") (name "/PWR_EN") (class "Default")
      (node (ref "R8") (pin "1") (pinfunction "1_1") (pintype "passive"))
      (node (ref "U3") (pin "44") (pinfunction "PC9/SEG18/ADC_IN0/SPI2_MISO_44") (pintype "passive"))
    )
    (net (code "32") (name "/RESET") (class "Default")
      (node (ref "C18") (pin "2") (pinfunction "2_2") (pintype "passive"))
      (node (ref "R18") (pin "1") (pinfunction "1_1") (pintype "passive"))
      (node (ref "R30") (pin "1") (pinfunction "1_1") (pintype "passive"))
      (node (ref "U3") (pin "1") (pinfunction "NRST_1") (pintype "passive"))
    )
    (net (code "33") (name "/STATE_MCU") (class "Default")
      (node (ref "U3") (pin "11") (pinfunction "I2CSMB_SCL/COM6/SEG30/PA6_11") (pintype "passive"))
    )
    (net (code "34") (name "/STATUS") (class "Default")
      (node (ref "U3") (pin "55") (pinfunction "ATIM_BRK1/ADC_IN2/FOUT0/(WKUP6)PD11_55") (pintype "passive+no_connect"))
    )
    (net (code "35") (name "/SVS") (class "Default")
      (node (ref "C22") (pin "2") (pinfunction "2_2") (pintype "passive"))
      (node (ref "R22") (pin "2") (pinfunction "2_2") (pintype "passive"))
      (node (ref "R24") (pin "1") (pinfunction "1_1") (pintype "passive"))
      (node (ref "U3") (pin "4") (pinfunction "ADC_IN10/SVS/(WKUP0)PA15_4") (pintype "passive"))
    )
    (net (code "36") (name "/SVS_EN") (class "Default")
      (node (ref "R21") (pin "1") (pinfunction "1_1") (pintype "passive"))
      (node (ref "U3") (pin "3") (pinfunction "COMP1_INP4/ADC_IN7/LPUART0_TX/UART0_TX/PA14_3") (pintype "passive"))
    )
    (net (code "37") (name "/SWCLK") (class "Default")
      (node (ref "J3") (pin "4") (pinfunction "4_4") (pintype "passive"))
      (node (ref "R2") (pin "1") (pinfunction "1_1") (pintype "passive"))
      (node (ref "U3") (pin "63") (pinfunction "UART2_RX/SWCLK/PD7_63") (pintype "passive"))
    )
    (net (code "38") (name "/SWDIO") (class "Default")
      (node (ref "J3") (pin "3") (pinfunction "3_3") (pintype "passive"))
      (node (ref "R1") (pin "1") (pinfunction "1_1") (pintype "passive"))
      (node (ref "U3") (pin "64") (pinfunction "UART2_TX/SWIO/PD8_64") (pintype "passive"))
    )
    (net (code "39") (name "/XT1") (class "Default")
      (node (ref "C33") (pin "2") (pinfunction "2_2") (pintype "passive"))
      (node (ref "U3") (pin "48") (pinfunction "XT32KO/PD9_48") (pintype "passive"))
      (node (ref "Y1") (pin "2") (pinfunction "P2_2") (pintype "passive"))
    )
    (net (code "40") (name "/XT2") (class "Default")
      (node (ref "C34") (pin "2") (pinfunction "2_2") (pintype "passive"))
      (node (ref "U3") (pin "49") (pinfunction "PD10/XT32KI_49") (pintype "passive"))
      (node (ref "Y1") (pin "1") (pinfunction "P1_1") (pintype "passive"))
    )
    (net (code "41") (name "GND") (class "Default")
      (node (ref "C1") (pin "2") (pinfunction "2_2") (pintype "passive"))
      (node (ref "C15") (pin "2") (pinfunction "2_2") (pintype "passive"))
      (node (ref "C16") (pin "1") (pinfunction "1_1") (pintype "passive"))
      (node (ref "C17") (pin "1") (pinfunction "1_1") (pintype "passive"))
      (node (ref "C18") (pin "1") (pinfunction "1_1") (pintype "passive"))
      (node (ref "C19") (pin "1") (pinfunction "1_1") (pintype "passive"))
      (node (ref "C2") (pin "2") (pinfunction "2_2") (pintype "passive"))
      (node (ref "C20") (pin "1") (pinfunction "1_1") (pintype "passive"))
      (node (ref "C21") (pin "1") (pinfunction "1_1") (pintype "passive"))
      (node (ref "C22") (pin "1") (pinfunction "1_1") (pintype "passive"))
      (node (ref "C23") (pin "1") (pinfunction "1_1") (pintype "passive"))
      (node (ref "C24") (pin "1") (pinfunction "1_1") (pintype "passive"))
      (node (ref "C25") (pin "1") (pinfunction "1_1") (pintype "passive"))
      (node (ref "C26") (pin "2") (pinfunction "2_2") (pintype "passive"))
      (node (ref "C3") (pin "2") (pinfunction "2_2") (pintype "passive"))
      (node (ref "C33") (pin "1") (pinfunction "1_1") (pintype "passive"))
      (node (ref "C34") (pin "1") (pinfunction "1_1") (pintype "passive"))
      (node (ref "C35") (pin "1") (pinfunction "1_1") (pintype "passive"))
      (node (ref "C36") (pin "2") (pinfunction "2_2") (pintype "passive"))
      (node (ref "C37") (pin "1") (pinfunction "1_1") (pintype "passive"))
      (node (ref "C38") (pin "1") (pinfunction "1_1") (pintype "passive"))
      (node (ref "C39") (pin "2") (pinfunction "2_2") (pintype "passive"))
      (node (ref "C4") (pin "2") (pinfunction "2_2") (pintype "passive"))
      (node (ref "C40") (pin "1") (pinfunction "1_1") (pintype "passive"))
      (node (ref "C41") (pin "1") (pinfunction "1_1") (pintype "passive"))
      (node (ref "C42") (pin "1") (pinfunction "1_1") (pintype "passive"))
      (node (ref "C43") (pin "2") (pinfunction "2_2") (pintype "passive"))
      (node (ref "C44") (pin "2") (pinfunction "2_2") (pintype "passive"))
      (node (ref "C47") (pin "2") (pinfunction "2_2") (pintype "passive"))
      (node (ref "C48") (pin "1") (pinfunction "1_1") (pintype "passive"))
      (node (ref "C49") (pin "1") (pinfunction "1_1") (pintype "passive"))
      (node (ref "C5") (pin "2") (pinfunction "2_2") (pintype "passive"))
      (node (ref "C51") (pin "1") (pinfunction "1_1") (pintype "passive"))
      (node (ref "C52") (pin "2") (pinfunction "2_2") (pintype "passive"))
      (node (ref "C53") (pin "2") (pinfunction "2_2") (pintype "passive"))
      (node (ref "C54") (pin "1") (pinfunction "1_1") (pintype "passive"))
      (node (ref "C55") (pin "2") (pinfunction "2_2") (pintype "passive"))
      (node (ref "C56") (pin "2") (pinfunction "2_2") (pintype "passive"))
      (node (ref "C57") (pin "2") (pinfunction "2_2") (pintype "passive"))
      (node (ref "C58") (pin "2") (pinfunction "2_2") (pintype "passive"))
      (node (ref "C59") (pin "2") (pinfunction "2_2") (pintype "passive"))
      (node (ref "C60") (pin "1") (pinfunction "1_1") (pintype "passive"))
      (node (ref "C8") (pin "2") (pinfunction "2_2") (pintype "passive"))
      (node (ref "C9") (pin "1") (pinfunction "1_1") (pintype "passive"))
      (node (ref "D3") (pin "1") (pinfunction "A_1") (pintype "passive"))
      (node (ref "J1") (pin "2") (pinfunction "2_2") (pintype "passive"))
      (node (ref "J2") (pin "1") (pinfunction "1_1") (pintype "passive"))
      (node (ref "J3") (pin "2") (pinfunction "2_2") (pintype "passive"))
      (node (ref "J4") (pin "3") (pinfunction "3_3") (pintype "passive"))
      (node (ref "J5") (pin "3") (pinfunction "3_3") (pintype "passive"))
      (node (ref "P1") (pin "2") (pinfunction "2_2") (pintype "passive"))
      (node (ref "Q10") (pin "2") (pinfunction "E_2") (pintype "passive"))
      (node (ref "Q6") (pin "2") (pinfunction "E_2") (pintype "passive"))
      (node (ref "Q9") (pin "3") (pinfunction "C_3") (pintype "passive"))
      (node (ref "R24") (pin "2") (pinfunction "2_2") (pintype "passive"))
      (node (ref "R36") (pin "1") (pinfunction "1_1") (pintype "passive"))
      (node (ref "R37") (pin "1") (pinfunction "1_1") (pintype "passive"))
      (node (ref "R44") (pin "1") (pinfunction "1_1") (pintype "passive"))
      (node (ref "U1") (pin "1") (pinfunction "GND_1") (pintype "passive"))
      (node (ref "U10") (pin "2") (pinfunction "2_2") (pintype "passive"))
      (node (ref "U11") (pin "3") (pinfunction "GND_3") (pintype "passive"))
      (node (ref "U3") (pin "33") (pinfunction "VSS_33") (pintype "passive"))
      (node (ref "U3") (pin "51") (pinfunction "VSS_51") (pintype "passive"))
      (node (ref "U3") (pin "53") (pinfunction "VREFN_53") (pintype "passive"))
      (node (ref "U4") (pin "1") (pinfunction "GND_1") (pintype "passive"))
      (node (ref "U6") (pin "9") (pinfunction "Pad_9") (pintype "passive"))
      (node (ref "U7") (pin "4") (pinfunction "VSS_4") (pintype "passive"))
      (node (ref "U8") (pin "2") (pinfunction "GND_2") (pintype "passive"))
      (node (ref "U8") (pin "6") (pinfunction "TOB_6") (pintype "passive"))
      (node (ref "U9") (pin "2") (pinfunction "2_2") (pintype "passive"))
    )
    (net (code "42") (name "GPRS_3.6V") (class "Default")
      (node (ref "C1") (pin "1") (pinfunction "1_1") (pintype "passive"))
      (node (ref "C2") (pin "1") (pinfunction "1_1") (pintype "passive"))
      (node (ref "C5") (pin "1") (pinfunction "1_1") (pintype "passive"))
      (node (ref "C8") (pin "1") (pinfunction "1_1") (pintype "passive"))
      (node (ref "Q3") (pin "3") (pinfunction "D_3") (pintype "passive"))
    )
    (net (code "43") (name "KEY_VCC") (class "Default")
      (node (ref "R14") (pin "2") (pinfunction "2_2") (pintype "passive"))
      (node (ref "U3") (pin "2") (pinfunction "COMP1_INP3/ADC_IN6/LPUART0_RX/UART0_RX/PA13_2") (pintype "passive"))
    )
    (net (code "44") (name "Net-(C60-Pad2)") (class "Default")
      (node (ref "C60") (pin "2") (pinfunction "2_2") (pintype "passive"))
      (node (ref "J3") (pin "5") (pinfunction "5_5") (pintype "passive"))
      (node (ref "R30") (pin "2") (pinfunction "2_2") (pintype "passive"))
    )
    (net (code "45") (name "Net-(D4-K)") (class "Default")
      (node (ref "D4") (pin "2") (pinfunction "K_2") (pintype "passive"))
      (node (ref "R29") (pin "1") (pinfunction "1_1") (pintype "passive"))
    )
    (net (code "46") (name "Net-(D6-A)") (class "Default")
      (node (ref "D6") (pin "1") (pinfunction "A_1") (pintype "passive"))
      (node (ref "R42") (pin "2") (pinfunction "2_2") (pintype "passive"))
    )
    (net (code "47") (name "Net-(D6-K)") (class "Default")
      (node (ref "D6") (pin "2") (pinfunction "K_2") (pintype "passive"))
      (node (ref "D7") (pin "1") (pinfunction "A_1") (pintype "passive"))
      (node (ref "Q7") (pin "3") (pinfunction "C_3") (pintype "passive"))
      (node (ref "R35") (pin "2") (pinfunction "2_2") (pintype "passive"))
      (node (ref "R39") (pin "2") (pinfunction "2_2") (pintype "passive"))
    )
    (net (code "48") (name "Net-(D7-K)") (class "Default")
      (node (ref "D7") (pin "2") (pinfunction "K_2") (pintype "passive"))
      (node (ref "R43") (pin "2") (pinfunction "2_2") (pintype "passive"))
    )
    (net (code "49") (name "Net-(J4-Pad4)") (class "Default")
      (node (ref "J4") (pin "4") (pinfunction "4_4") (pintype "passive"))
      (node (ref "R48") (pin "2") (pinfunction "2_2") (pintype "passive"))
    )
    (net (code "50") (name "Net-(J4-Pad5)") (class "Default")
      (node (ref "J4") (pin "5") (pinfunction "5_5") (pintype "passive"))
      (node (ref "R49") (pin "2") (pinfunction "2_2") (pintype "passive"))
    )
    (net (code "51") (name "Net-(J5-Pad2)") (class "Default")
      (node (ref "J5") (pin "2") (pinfunction "2_2") (pintype "passive"))
      (node (ref "R45") (pin "2") (pinfunction "2_2") (pintype "passive"))
    )
    (net (code "52") (name "Net-(J5-Pad4)") (class "Default")
      (node (ref "J5") (pin "4") (pinfunction "4_4") (pintype "passive"))
      (node (ref "R46") (pin "2") (pinfunction "2_2") (pintype "passive"))
    )
    (net (code "53") (name "Net-(J5-Pad5)") (class "Default")
      (node (ref "J5") (pin "5") (pinfunction "5_5") (pintype "passive"))
      (node (ref "R47") (pin "2") (pinfunction "2_2") (pintype "passive"))
    )
    (net (code "54") (name "Net-(KT1-Pad1)") (class "Default")
      (node (ref "KT1") (pin "1") (pinfunction "1_1") (pintype "passive"))
      (node (ref "R50") (pin "1") (pinfunction "1_1") (pintype "passive"))
    )
    (net (code "55") (name "Net-(Q3-G)") (class "Default")
      (node (ref "Q3") (pin "1") (pinfunction "G_1") (pintype "passive"))
      (node (ref "R7") (pin "1") (pinfunction "1_1") (pintype "passive"))
      (node (ref "R8") (pin "2") (pinfunction "2_2") (pintype "passive"))
    )
    (net (code "56") (name "Net-(Q3-S)") (class "Default")
      (node (ref "C4") (pin "1") (pinfunction "1_1") (pintype "passive"))
      (node (ref "Q3") (pin "2") (pinfunction "S_2") (pintype "passive"))
      (node (ref "R7") (pin "2") (pinfunction "2_2") (pintype "passive"))
      (node (ref "U1") (pin "3") (pinfunction "Vout_3") (pintype "passive"))
    )
    (net (code "57") (name "Net-(Q5-B)") (class "Default")
      (node (ref "Q5") (pin "1") (pinfunction "B_1") (pintype "passive"))
      (node (ref "R20") (pin "2") (pinfunction "2_2") (pintype "passive"))
    )
    (net (code "58") (name "Net-(Q5-C)") (class "Default")
      (node (ref "Q5") (pin "3") (pinfunction "C_3") (pintype "passive"))
      (node (ref "R22") (pin "1") (pinfunction "1_1") (pintype "passive"))
    )
    (net (code "59") (name "Net-(Q6-B)") (class "Default")
      (node (ref "Q6") (pin "1") (pinfunction "B_1") (pintype "passive"))
      (node (ref "R21") (pin "2") (pinfunction "2_2") (pintype "passive"))
    )
    (net (code "60") (name "Net-(Q6-C)") (class "Default")
      (node (ref "Q6") (pin "3") (pinfunction "C_3") (pintype "passive"))
      (node (ref "R19") (pin "1") (pinfunction "1_1") (pintype "passive"))
      (node (ref "R20") (pin "1") (pinfunction "1_1") (pintype "passive"))
    )
    (net (code "61") (name "Net-(Q7-B)") (class "Default")
      (node (ref "Q7") (pin "1") (pinfunction "B_1") (pintype "passive"))
      (node (ref "R33") (pin "2") (pinfunction "2_2") (pintype "passive"))
    )
    (net (code "62") (name "Net-(Q8-B)") (class "Default")
      (node (ref "Q8") (pin "1") (pinfunction "B_1") (pintype "passive"))
      (node (ref "R38") (pin "2") (pinfunction "2_2") (pintype "passive"))
    )
    (net (code "63") (name "Net-(Q9-B)") (class "Default")
      (node (ref "Q9") (pin "1") (pinfunction "B_1") (pintype "passive"))
      (node (ref "R40") (pin "2") (pinfunction "2_2") (pintype "passive"))
    )
    (net (code "64") (name "Net-(Q9-E)") (class "Default")
      (node (ref "Q9") (pin "2") (pinfunction "E_2") (pintype "passive"))
      (node (ref "R43") (pin "1") (pinfunction "1_1") (pintype "passive"))
    )
    (net (code "65") (name "Net-(Q10-B)") (class "Default")
      (node (ref "C44") (pin "1") (pinfunction "1_1") (pintype "passive"))
      (node (ref "Q10") (pin "1") (pinfunction "B_1") (pintype "passive"))
      (node (ref "R42") (pin "1") (pinfunction "1_1") (pintype "passive"))
      (node (ref "R44") (pin "2") (pinfunction "2_2") (pintype "passive"))
    )
    (net (code "66") (name "Net-(Q12-D)") (class "Default")
      (node (ref "C26") (pin "1") (pinfunction "1_1") (pintype "passive"))
      (node (ref "C39") (pin "1") (pinfunction "1_1") (pintype "passive"))
      (node (ref "C9") (pin "2") (pinfunction "2_2") (pintype "passive"))
      (node (ref "Q12") (pin "3") (pinfunction "D_3") (pintype "passive"))
      (node (ref "U8") (pin "4") (pinfunction "AHLB_4") (pintype "passive"))
      (node (ref "U8") (pin "5") (pinfunction "VCC_5") (pintype "passive"))
    )
    (net (code "67") (name "Net-(Q12-G)") (class "Default")
      (node (ref "Q12") (pin "1") (pinfunction "G_1") (pintype "passive"))
      (node (ref "R14") (pin "1") (pinfunction "1_1") (pintype "passive"))
      (node (ref "R9") (pin "1") (pinfunction "1_1") (pintype "passive"))
    )
    (net (code "68") (name "Net-(U3-VDD15)") (class "Default")
      (node (ref "C23") (pin "2") (pinfunction "2_2") (pintype "passive"))
      (node (ref "U3") (pin "50") (pinfunction "VDD15_50") (pintype "passive"))
    )
    (net (code "69") (name "Net-(U4-Vin)") (class "Default")
      (node (ref "C15") (pin "1") (pinfunction "1_1") (pintype "passive"))
      (node (ref "D1") (pin "2") (pinfunction "2_2") (pintype "passive"))
      (node (ref "U4") (pin "2") (pinfunction "Vin_2") (pintype "passive"))
    )
    (net (code "70") (name "Net-(U8-KEY)") (class "Default")
      (node (ref "C40") (pin "2") (pinfunction "2_2") (pintype "passive"))
      (node (ref "R50") (pin "2") (pinfunction "2_2") (pintype "passive"))
      (node (ref "U8") (pin "3") (pinfunction "KEY_3") (pintype "passive"))
    )
    (net (code "71") (name "VBAT") (class "Default")
      (node (ref "D1") (pin "1") (pinfunction "1_1") (pintype "passive"))
      (node (ref "D2") (pin "1") (pinfunction "1_1") (pintype "passive"))
      (node (ref "D3") (pin "2") (pinfunction "K_2") (pintype "passive"))
      (node (ref "J1") (pin "1") (pinfunction "1_1") (pintype "passive"))
      (node (ref "P1") (pin "1") (pinfunction "1_1") (pintype "passive"))
      (node (ref "Q5") (pin "2") (pinfunction "E_2") (pintype "passive"))
      (node (ref "R19") (pin "2") (pinfunction "2_2") (pintype "passive"))
    )
    (net (code "72") (name "VCC") (class "Default")
      (node (ref "C16") (pin "2") (pinfunction "2_2") (pintype "passive"))
      (node (ref "C17") (pin "2") (pinfunction "2_2") (pintype "passive"))
      (node (ref "C20") (pin "2") (pinfunction "2_2") (pintype "passive"))
      (node (ref "C21") (pin "2") (pinfunction "2_2") (pintype "passive"))
      (node (ref "C24") (pin "2") (pinfunction "2_2") (pintype "passive"))
      (node (ref "C25") (pin "2") (pinfunction "2_2") (pintype "passive"))
      (node (ref "C35") (pin "2") (pinfunction "2_2") (pintype "passive"))
      (node (ref "C41") (pin "2") (pinfunction "2_2") (pintype "passive"))
      (node (ref "C42") (pin "2") (pinfunction "2_2") (pintype "passive"))
      (node (ref "C49") (pin "2") (pinfunction "2_2") (pintype "passive"))
      (node (ref "C51") (pin "2") (pinfunction "2_2") (pintype "passive"))
      (node (ref "C54") (pin "2") (pinfunction "2_2") (pintype "passive"))
      (node (ref "C59") (pin "1") (pinfunction "1_1") (pintype "passive"))
      (node (ref "D4") (pin "1") (pinfunction "A_1") (pintype "passive"))
      (node (ref "J3") (pin "1") (pinfunction "1_1") (pintype "passive"))
      (node (ref "J5") (pin "1") (pinfunction "1_1") (pintype "passive"))
      (node (ref "Q12") (pin "2") (pinfunction "S_2") (pintype "passive"))
      (node (ref "Q7") (pin "2") (pinfunction "E_2") (pintype "passive"))
      (node (ref "Q8") (pin "2") (pinfunction "E_2") (pintype "passive"))
      (node (ref "R1") (pin "2") (pinfunction "2_2") (pintype "passive"))
      (node (ref "R18") (pin "2") (pinfunction "2_2") (pintype "passive"))
      (node (ref "R2") (pin "2") (pinfunction "2_2") (pintype "passive"))
      (node (ref "R9") (pin "2") (pinfunction "2_2") (pintype "passive"))
      (node (ref "U10") (pin "1") (pinfunction "1_1") (pintype "passive"))
      (node (ref "U11") (pin "1") (pinfunction "VDD_1") (pintype "passive"))
      (node (ref "U3") (pin "34") (pinfunction "VDD_34") (pintype "passive"))
      (node (ref "U3") (pin "52") (pinfunction "VDD_52") (pintype "passive"))
      (node (ref "U3") (pin "54") (pinfunction "VREFP_54") (pintype "passive"))
      (node (ref "U4") (pin "3") (pinfunction "Vout_3") (pintype "passive"))
      (node (ref "U6") (pin "8") (pinfunction "VCC_8") (pintype "passive"))
      (node (ref "U9") (pin "1") (pinfunction "1_1") (pintype "passive"))
    )
    (net (code "73") (name "VCC_M") (class "Default")
      (node (ref "C19") (pin "2") (pinfunction "2_2") (pintype "passive"))
      (node (ref "C3") (pin "1") (pinfunction "1_1") (pintype "passive"))
      (node (ref "C36") (pin "1") (pinfunction "1_1") (pintype "passive"))
      (node (ref "D2") (pin "2") (pinfunction "2_2") (pintype "passive"))
      (node (ref "U1") (pin "2") (pinfunction "Vin_2") (pintype "passive"))
      (node (ref "U6") (pin "1") (pinfunction "VM_1") (pintype "passive"))
    )
    (net (code "74") (name "unconnected-(U3-ADC_IN4{slash}UART5_TX{slash}SEG23{slash}PD1-Pad57)") (class "Default")
      (node (ref "U3") (pin "57") (pinfunction "ADC_IN4/UART5_TX/SEG23/PD1_57") (pintype "passive+no_connect"))
    )
    (net (code "75") (name "unconnected-(U3-ATIM_BRK2{slash}ANATST{slash}PD6(WKUP7)-Pad62)") (class "Default")
      (node (ref "U3") (pin "62") (pinfunction "ATIM_BRK2/ANATST/PD6(WKUP7)_62") (pintype "passive"))
    )
    (net (code "76") (name "unconnected-(U3-ATIM_CH3{slash}COMP1_INN1{slash}LPT32_ETR{slash}SEG2{slash}(WKUP1)PA10-Pad15)") (class "Default")
      (node (ref "U3") (pin "15") (pinfunction "ATIM_CH3/COMP1_INN1/LPT32_ETR/SEG2/(WKUP1)PA10_15") (pintype "passive"))
    )
    (net (code "77") (name "unconnected-(U3-COMP2_INN1{slash}GPT1_CH3{slash}COM4{slash}SEG28{slash}PA4-Pad9)") (class "Default")
      (node (ref "U3") (pin "9") (pinfunction "COMP2_INN1/GPT1_CH3/COM4/SEG28/PA4_9") (pintype "passive"))
    )
    (net (code "78") (name "unconnected-(U3-PB3{slash}UART4_TX{slash}ATIM_CH2N-Pad21)") (class "Default")
      (node (ref "U3") (pin "21") (pinfunction "PB3/UART4_TX/ATIM_CH2N_21") (pintype "passive"))
    )
    (net (code "79") (name "unconnected-(U3-PB6{slash}SEG5{slash}ATIM_CH3-Pad24)") (class "Default")
      (node (ref "U3") (pin "24") (pinfunction "PB6/SEG5/ATIM_CH3_24") (pintype "passive"))
    )
    (net (code "80") (name "unconnected-(U3-PB8{slash}SEG7{slash}SPI1_SSN{slash}ATIM_CH3N-Pad26)") (class "Default")
      (node (ref "U3") (pin "26") (pinfunction "PB8/SEG7/SPI1_SSN/ATIM_CH3N_26") (pintype "passive"))
    )
    (net (code "81") (name "unconnected-(U3-PB9{slash}SEG8{slash}SPI1_SCK{slash}GPT0_ETR{slash}ANATST-Pad27)") (class "Default")
      (node (ref "U3") (pin "27") (pinfunction "PB9/SEG8/SPI1_SCK/GPT0_ETR/ANATST_27") (pintype "passive"))
    )
    (net (code "82") (name "unconnected-(U3-PB10{slash}SEG9{slash}SPI1_MISO{slash}GPT0_CH1-Pad28)") (class "Default")
      (node (ref "U3") (pin "28") (pinfunction "PB10/SEG9/SPI1_MISO/GPT0_CH1_28") (pintype "passive"))
    )
    (net (code "83") (name "unconnected-(U3-PC0{slash}GPT1_CH1{slash}I2CSMB_SCL-Pad35)") (class "Default")
      (node (ref "U3") (pin "35") (pinfunction "PC0/GPT1_CH1/I2CSMB_SCL_35") (pintype "passive"))
    )
    (net (code "84") (name "unconnected-(U3-PC1{slash}GPT1_CH2{slash}I2CSMB_SDA-Pad36)") (class "Default")
      (node (ref "U3") (pin "36") (pinfunction "PC1/GPT1_CH2/I2CSMB_SDA_36") (pintype "passive"))
    )
    (net (code "85") (name "unconnected-(U3-PC2{slash}XTHIN{slash}UART1_RX{slash}LPUART1_RX-Pad37)") (class "Default")
      (node (ref "U3") (pin "37") (pinfunction "PC2/XTHIN/UART1_RX/LPUART1_RX_37") (pintype "passive+no_connect"))
    )
    (net (code "86") (name "unconnected-(U3-PC3{slash}XTHOUT{slash}UART1_TX{slash}LPUART1_TX-Pad38)") (class "Default")
      (node (ref "U3") (pin "38") (pinfunction "PC3/XTHOUT/UART1_TX/LPUART1_TX_38") (pintype "passive+no_connect"))
    )
    (net (code "87") (name "unconnected-(U3-PC5{slash}SEG14{slash}UART5_TX{slash}SCL-Pad40)") (class "Default")
      (node (ref "U3") (pin "40") (pinfunction "PC5/SEG14/UART5_TX/SCL_40") (pintype "passive+no_connect"))
    )
    (net (code "88") (name "unconnected-(U3-PC6(WKUP4){slash}SEG15{slash}ADC_IN11{slash}GPT1_ETR{slash}I2CSMB_ALERT-Pad41)") (class "Default")
      (node (ref "U3") (pin "41") (pinfunction "PC6(WKUP4)/SEG15/ADC_IN11/GPT1_ETR/I2CSMB_ALERT_41") (pintype "passive"))
    )
    (net (code "89") (name "unconnected-(U3-PC8{slash}SEG17{slash}ADC_IN9{slash}SPI2_SCK-Pad43)") (class "Default")
      (node (ref "U3") (pin "43") (pinfunction "PC8/SEG17/ADC_IN9/SPI2_SCK_43") (pintype "passive"))
    )
    (net (code "90") (name "unconnected-(U3-PC12{slash}SEG21{slash}U7816IO{slash}GPT0_CH4-Pad47)") (class "Default")
      (node (ref "U3") (pin "47") (pinfunction "PC12/SEG21/U7816IO/GPT0_CH4_47") (pintype "passive"))
    )
  )
)
